# power.net
KiCad netlist of a schematic drawn in EAGLE
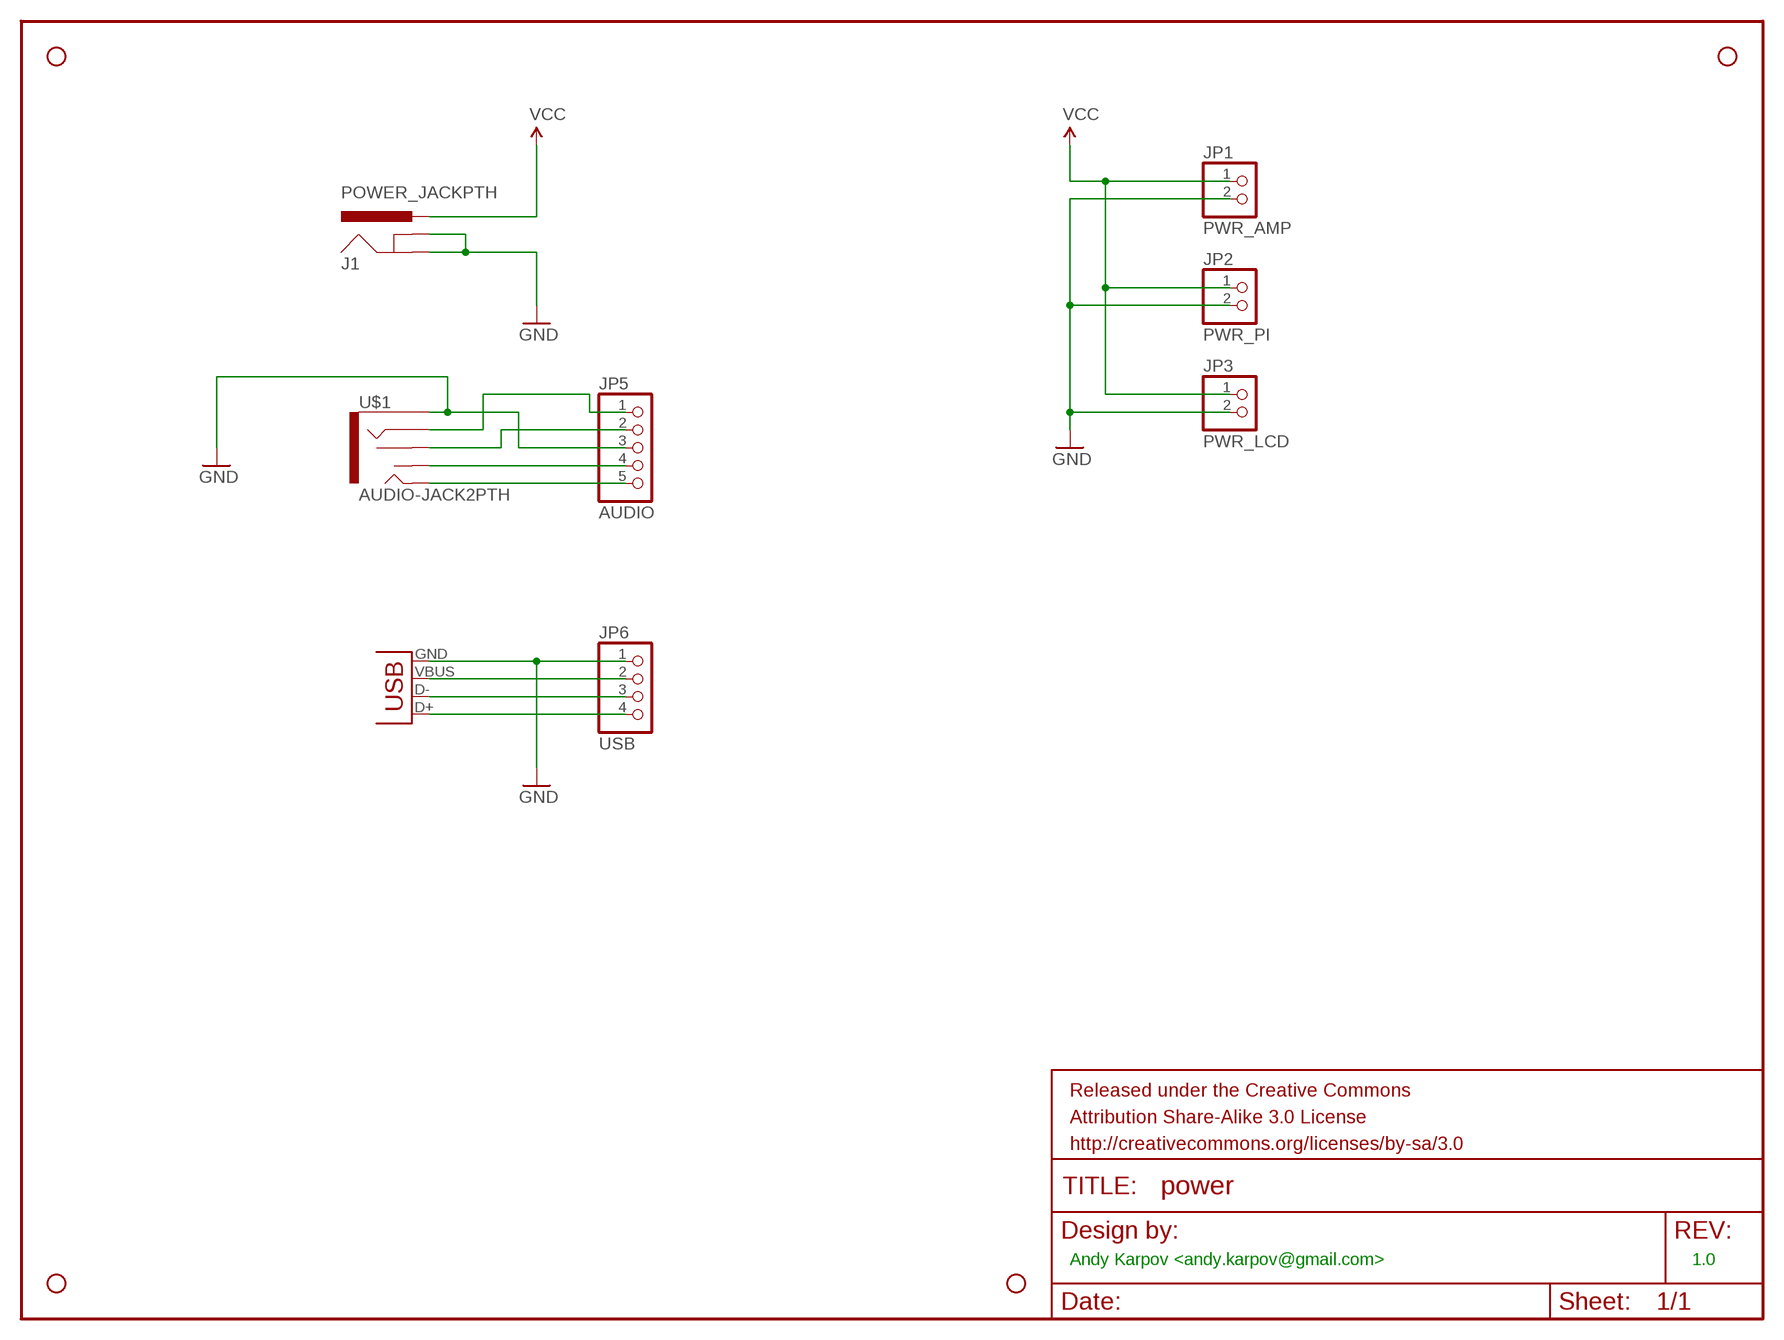
[diagram p0: schematic, sheet 1]

(export (version "E")
  (design (tool "Eeschema 10.0.6"))
  (components
    (comp (ref "FRAME1")
      (value "FRAME-LETTER")
      (footprint "eagle-import:CREATIVE_COMMONS")
      (libsource (lib "eagle-import") (part "FRAME-LETTER"))
    )
    (comp (ref "J1")
      (value "POWER_JACKPTH")
      (footprint "eagle-import:POWER_JACK_PTH")
      (libsource (lib "eagle-import") (part "POWER_JACKPTH"))
    )
    (comp (ref "JP1")
      (value "PWR_AMP")
      (footprint "eagle-import:1X02")
      (libsource (lib "eagle-import") (part "PINHD-1X2"))
    )
    (comp (ref "JP2")
      (value "PWR_PI")
      (footprint "eagle-import:1X02")
      (libsource (lib "eagle-import") (part "PINHD-1X2"))
    )
    (comp (ref "JP3")
      (value "PWR_LCD")
      (footprint "eagle-import:1X02")
      (libsource (lib "eagle-import") (part "PINHD-1X2"))
    )
    (comp (ref "JP4")
      (value "USB-B")
      (footprint "eagle-import:USB-B-PTH")
      (libsource (lib "eagle-import") (part "USBPTH"))
    )
    (comp (ref "JP5")
      (value "AUDIO")
      (footprint "eagle-import:1X05")
      (libsource (lib "eagle-import") (part "PINHD-1X5"))
    )
    (comp (ref "JP6")
      (value "USB")
      (footprint "eagle-import:1X04")
      (libsource (lib "eagle-import") (part "PINHD-1X4"))
    )
    (comp (ref "STANDOFF1")
      (value "STAND-OFF")
      (footprint "eagle-import:STAND-OFF")
      (libsource (lib "eagle-import") (part "STAND-OFF"))
    )
    (comp (ref "STANDOFF2")
      (value "STAND-OFF")
      (footprint "eagle-import:STAND-OFF")
      (libsource (lib "eagle-import") (part "STAND-OFF"))
    )
    (comp (ref "STANDOFF3")
      (value "STAND-OFF")
      (footprint "eagle-import:STAND-OFF")
      (libsource (lib "eagle-import") (part "STAND-OFF"))
    )
    (comp (ref "STANDOFF4")
      (value "STAND-OFF")
      (footprint "eagle-import:STAND-OFF")
      (libsource (lib "eagle-import") (part "STAND-OFF"))
    )
    (comp (ref "U$1")
      (value "AUDIO-JACK2PTH")
      (footprint "eagle-import:AUDIO-JACK")
      (libsource (lib "eagle-import") (part "AUDIO-JACK2PTH"))
    )
  )
  (nets
    (net (code "1") (name "GND") (class "Default")
      (node (ref "J1") (pin "GND") (pinfunction "GND_GND") (pintype "bidirectional"))
      (node (ref "J1") (pin "GNDBREAK") (pinfunction "GNDBREAK_GNDBREAK") (pintype "bidirectional"))
      (node (ref "JP1") (pin "2") (pinfunction "2_2") (pintype "passive"))
      (node (ref "JP2") (pin "2") (pinfunction "2_2") (pintype "passive"))
      (node (ref "JP3") (pin "2") (pinfunction "2_2") (pintype "passive"))
      (node (ref "JP4") (pin "GND") (pinfunction "GND_GND") (pintype "bidirectional"))
      (node (ref "JP5") (pin "3") (pinfunction "3_3") (pintype "passive"))
      (node (ref "JP6") (pin "1") (pinfunction "1_1") (pintype "passive"))
      (node (ref "U$1") (pin "SLEEVE") (pinfunction "SLEEVE_SLEEVE") (pintype "bidirectional"))
    )
    (net (code "2") (name "Net-(JP4-PadD+)") (class "Default")
      (node (ref "JP4") (pin "D+") (pinfunction "D+_D+") (pintype "bidirectional"))
      (node (ref "JP6") (pin "4") (pinfunction "4_4") (pintype "passive"))
    )
    (net (code "3") (name "Net-(JP4-PadD-)") (class "Default")
      (node (ref "JP4") (pin "D-") (pinfunction "D-_D-") (pintype "bidirectional"))
      (node (ref "JP6") (pin "3") (pinfunction "3_3") (pintype "passive"))
    )
    (net (code "4") (name "Net-(JP4-PadVBUS)") (class "Default")
      (node (ref "JP4") (pin "VBUS") (pinfunction "VBUS_VBUS") (pintype "bidirectional"))
      (node (ref "JP6") (pin "2") (pinfunction "2_2") (pintype "passive"))
    )
    (net (code "5") (name "Net-(JP5-Pad1)") (class "Default")
      (node (ref "JP5") (pin "1") (pinfunction "1_1") (pintype "passive"))
      (node (ref "U$1") (pin "RING") (pinfunction "RING_RING") (pintype "bidirectional"))
    )
    (net (code "6") (name "Net-(JP5-Pad2)") (class "Default")
      (node (ref "JP5") (pin "2") (pinfunction "2_2") (pintype "passive"))
      (node (ref "U$1") (pin "RSH") (pinfunction "RSH_RSH") (pintype "bidirectional"))
    )
    (net (code "7") (name "Net-(JP5-Pad4)") (class "Default")
      (node (ref "JP5") (pin "4") (pinfunction "4_4") (pintype "passive"))
      (node (ref "U$1") (pin "TSH") (pinfunction "TSH_TSH") (pintype "bidirectional"))
    )
    (net (code "8") (name "Net-(JP5-Pad5)") (class "Default")
      (node (ref "JP5") (pin "5") (pinfunction "5_5") (pintype "passive"))
      (node (ref "U$1") (pin "TIP") (pinfunction "TIP_TIP") (pintype "bidirectional"))
    )
    (net (code "9") (name "VCC") (class "Default")
      (node (ref "J1") (pin "PWR") (pinfunction "PWR_PWR") (pintype "bidirectional"))
      (node (ref "JP1") (pin "1") (pinfunction "1_1") (pintype "passive"))
      (node (ref "JP2") (pin "1") (pinfunction "1_1") (pintype "passive"))
      (node (ref "JP3") (pin "1") (pinfunction "1_1") (pintype "passive"))
    )
  )
)
